# ZeeSoC_Touch_Shield_v1_0.net
KiCad netlist of a schematic drawn in EAGLE
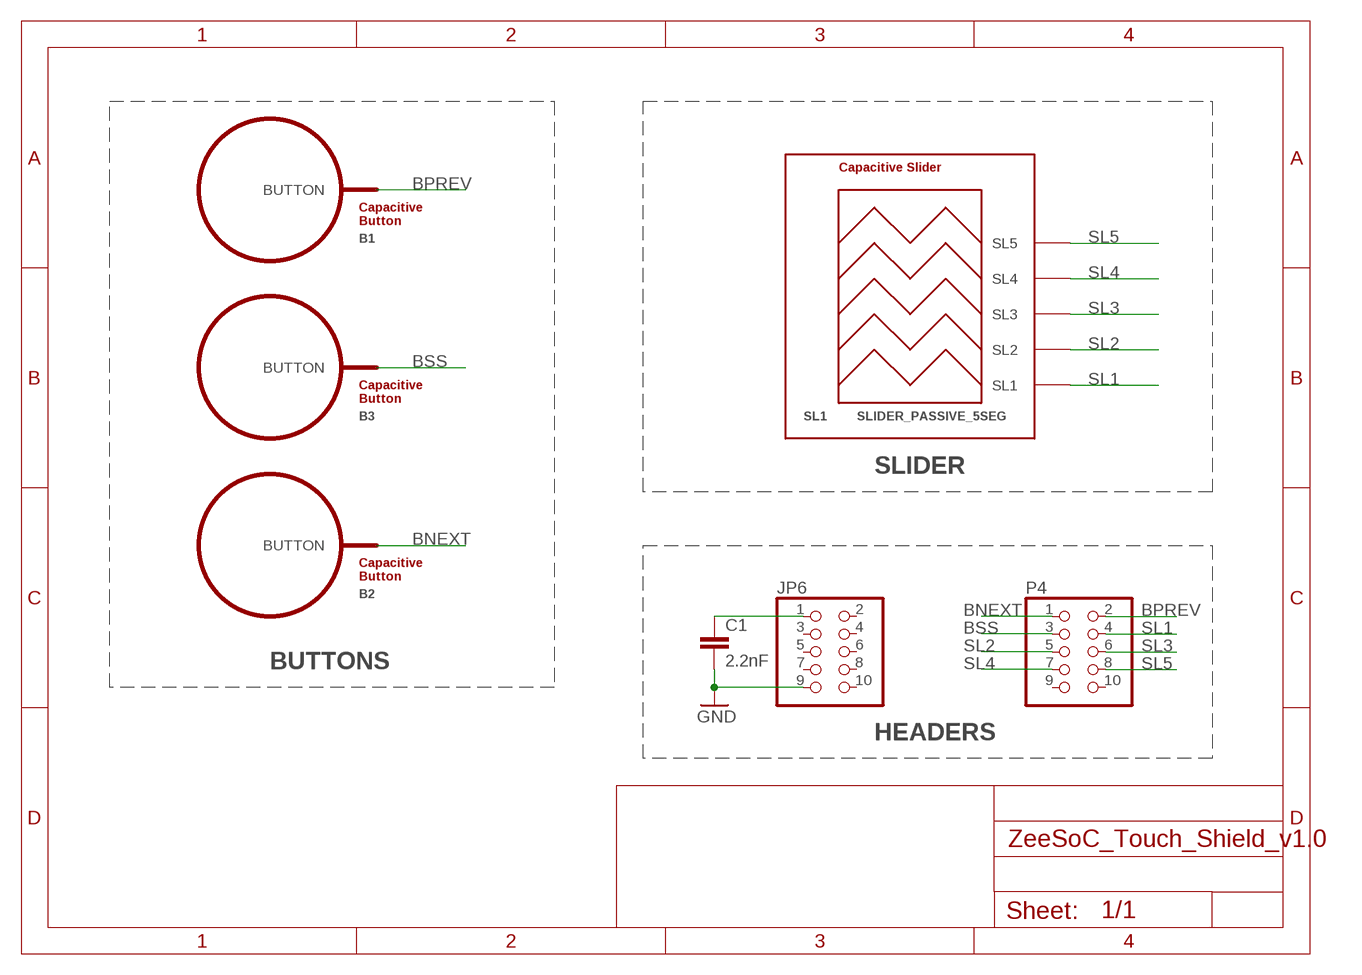
[diagram p0: schematic, sheet 1]

(export (version "E")
  (design (tool "Eeschema 10.0.6"))
  (components
    (comp (ref "B1")
      (value "BUTTON_PASSIVE8MM")
      (footprint "eagle-import:BUTTON_PASSIVE_8MM")
      (libsource (lib "eagle-import") (part "BUTTON_PASSIVE8MM"))
    )
    (comp (ref "B2")
      (value "BUTTON_PASSIVE8MM")
      (footprint "eagle-import:BUTTON_PASSIVE_8MM")
      (libsource (lib "eagle-import") (part "BUTTON_PASSIVE8MM"))
    )
    (comp (ref "B3")
      (value "BUTTON_PASSIVE8MM")
      (footprint "eagle-import:BUTTON_PASSIVE_8MM")
      (libsource (lib "eagle-import") (part "BUTTON_PASSIVE8MM"))
    )
    (comp (ref "C1")
      (value "2.2nF")
      (footprint "eagle-import:0603-CAP")
      (libsource (lib "eagle-import") (part "CAP0603-CAP"))
    )
    (comp (ref "JP6")
      (value "PINHD-2X5")
      (footprint "eagle-import:2X05")
      (libsource (lib "eagle-import") (part "PINHD-2X5"))
    )
    (comp (ref "P4")
      (value "PINHD-2X5")
      (footprint "eagle-import:2X05")
      (libsource (lib "eagle-import") (part "PINHD-2X5"))
    )
    (comp (ref "SL1")
      (value "SLIDER_PASSIVE_5SEG")
      (footprint "eagle-import:SLIDER_PASSIVE_5SEG_12MM")
      (libsource (lib "eagle-import") (part "SLIDER_PASSIVE_5SEG"))
    )
  )
  (nets
    (net (code "1") (name "/BNEXT") (class "Default")
      (node (ref "B2") (pin "BUTTON") (pinfunction "BUTTON_BUTTON") (pintype "passive"))
      (node (ref "P4") (pin "1") (pinfunction "1_1") (pintype "passive"))
    )
    (net (code "2") (name "/BPREV") (class "Default")
      (node (ref "B1") (pin "BUTTON") (pinfunction "BUTTON_BUTTON") (pintype "passive"))
      (node (ref "P4") (pin "2") (pinfunction "2_2") (pintype "passive"))
    )
    (net (code "3") (name "/BSS") (class "Default")
      (node (ref "B3") (pin "BUTTON") (pinfunction "BUTTON_BUTTON") (pintype "passive"))
      (node (ref "P4") (pin "3") (pinfunction "3_3") (pintype "passive"))
    )
    (net (code "4") (name "/SL1") (class "Default")
      (node (ref "P4") (pin "4") (pinfunction "4_4") (pintype "passive"))
      (node (ref "SL1") (pin "SL1") (pinfunction "SL1_SL1") (pintype "passive"))
    )
    (net (code "5") (name "/SL2") (class "Default")
      (node (ref "P4") (pin "5") (pinfunction "5_5") (pintype "passive"))
      (node (ref "SL1") (pin "SL2") (pinfunction "SL2_SL2") (pintype "passive"))
    )
    (net (code "6") (name "/SL3") (class "Default")
      (node (ref "P4") (pin "6") (pinfunction "6_6") (pintype "passive"))
      (node (ref "SL1") (pin "SL3") (pinfunction "SL3_SL3") (pintype "passive"))
    )
    (net (code "7") (name "/SL4") (class "Default")
      (node (ref "P4") (pin "7") (pinfunction "7_7") (pintype "passive"))
      (node (ref "SL1") (pin "SL4") (pinfunction "SL4_SL4") (pintype "passive"))
    )
    (net (code "8") (name "/SL5") (class "Default")
      (node (ref "P4") (pin "8") (pinfunction "8_8") (pintype "passive"))
      (node (ref "SL1") (pin "SL5") (pinfunction "SL5_SL5") (pintype "passive"))
    )
    (net (code "9") (name "GND") (class "Default")
      (node (ref "C1") (pin "2") (pinfunction "2_2") (pintype "passive"))
      (node (ref "JP6") (pin "9") (pinfunction "9_9") (pintype "passive"))
    )
    (net (code "10") (name "Net-(C1-Pad1)") (class "Default")
      (node (ref "C1") (pin "1") (pinfunction "1_1") (pintype "passive"))
      (node (ref "JP6") (pin "1") (pinfunction "1_1") (pintype "passive"))
    )
    (net (code "11") (name "unconnected-(JP6-Pad2)") (class "Default")
      (node (ref "JP6") (pin "2") (pinfunction "2_2") (pintype "passive"))
    )
    (net (code "12") (name "unconnected-(JP6-Pad3)") (class "Default")
      (node (ref "JP6") (pin "3") (pinfunction "3_3") (pintype "passive"))
    )
    (net (code "13") (name "unconnected-(JP6-Pad4)") (class "Default")
      (node (ref "JP6") (pin "4") (pinfunction "4_4") (pintype "passive"))
    )
    (net (code "14") (name "unconnected-(JP6-Pad5)") (class "Default")
      (node (ref "JP6") (pin "5") (pinfunction "5_5") (pintype "passive"))
    )
    (net (code "15") (name "unconnected-(JP6-Pad6)") (class "Default")
      (node (ref "JP6") (pin "6") (pinfunction "6_6") (pintype "passive"))
    )
    (net (code "16") (name "unconnected-(JP6-Pad7)") (class "Default")
      (node (ref "JP6") (pin "7") (pinfunction "7_7") (pintype "passive"))
    )
    (net (code "17") (name "unconnected-(JP6-Pad8)") (class "Default")
      (node (ref "JP6") (pin "8") (pinfunction "8_8") (pintype "passive"))
    )
    (net (code "18") (name "unconnected-(JP6-Pad10)") (class "Default")
      (node (ref "JP6") (pin "10") (pinfunction "10_10") (pintype "passive"))
    )
    (net (code "19") (name "unconnected-(P4-Pad9)") (class "Default")
      (node (ref "P4") (pin "9") (pinfunction "9_9") (pintype "passive"))
    )
    (net (code "20") (name "unconnected-(P4-Pad10)") (class "Default")
      (node (ref "P4") (pin "10") (pinfunction "10_10") (pintype "passive"))
    )
  )
)
